# LED.net
KiCad netlist of a schematic drawn in Altium Designer
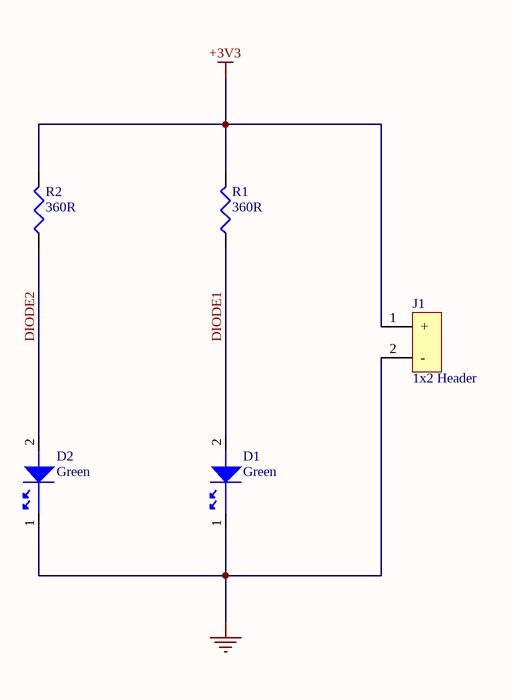
[diagram p0: LED.SchDoc]

(export (version "E")
  (design (tool "Eeschema 10.0.6"))
  (components
    (comp (ref "D1")
      (value "Green")
      (footprint "LED0603G")
      (description "APG1608CGKC/T Green LED; 570 nm 1608 (0603) Clear; Rectangle Lens SMD package")
      (fields
        (field (name "MANUFACTURER") "Kingbright")
        (field (name "MANUFACTURER PART NUMBER") "APG1608CGKC/T")
      )
      (libsource (lib "LED_Schlib1") (part "APG1608CGKC/T"))
    )
    (comp (ref "D2")
      (value "Green")
      (footprint "LED0603G")
      (description "APG1608CGKC/T Green LED; 570 nm 1608 (0603) Clear; Rectangle Lens SMD package")
      (fields
        (field (name "MANUFACTURER") "Kingbright")
        (field (name "MANUFACTURER PART NUMBER") "APG1608CGKC/T")
      )
      (libsource (lib "LED_Schlib1") (part "APG1608CGKC/T"))
    )
    (comp (ref "J1")
      (value "1x2 Header")
      (footprint "Header1x2")
      (description "KK 254 Wire-to-Board Header, Vertical, with Friction Lock, 2 Circuits, Gold (Au) Plating")
      (fields (field (name "MANUFACTURER") "Molex") (field (name "MANUFACTURER PART NUMBER") "22-29-2021"))
      (libsource (lib "LED_Schlib1") (part "22-29-2021"))
    )
    (comp (ref "R1")
      (value "360R")
      (footprint "R0805")
      (description "Res Thick Film 0805 36 Ohm 1% 1/8W ±100ppm/°C Molded SMD SMD Paper T/R")
      (fields
        (field (name "MANUFACTURER") "Vishay")
        (field (name "MANUFACTURER PART NUMBER") "CRCW080536R0FKEA")
      )
      (libsource (lib "LED_Schlib1") (part "CRCW080536R0FKEA"))
    )
    (comp (ref "R2")
      (value "360R")
      (footprint "R0805")
      (description "Res Thick Film 0805 36 Ohm 1% 1/8W ±100ppm/°C Molded SMD SMD Paper T/R")
      (fields
        (field (name "MANUFACTURER") "Vishay")
        (field (name "MANUFACTURER PART NUMBER") "CRCW080536R0FKEA")
      )
      (libsource (lib "LED_Schlib1") (part "CRCW080536R0FKEA"))
    )
  )
  (nets
    (net (code "1") (name "+3V3") (class "Default")
      (node (ref "J1") (pin "1") (pinfunction "+_1") (pintype "passive"))
      (node (ref "R1") (pin "2") (pinfunction "2_2") (pintype "passive"))
      (node (ref "R2") (pin "2") (pinfunction "2_2") (pintype "passive"))
    )
    (net (code "2") (name "/DIODE1") (class "Default")
      (node (ref "D1") (pin "2") (pinfunction "2_2") (pintype "passive"))
      (node (ref "R1") (pin "1") (pinfunction "1_1") (pintype "passive"))
    )
    (net (code "3") (name "/DIODE2") (class "Default")
      (node (ref "D2") (pin "2") (pinfunction "2_2") (pintype "passive"))
      (node (ref "R2") (pin "1") (pinfunction "1_1") (pintype "passive"))
    )
    (net (code "4") (name "GND") (class "Default")
      (node (ref "D1") (pin "1") (pinfunction "1_1") (pintype "passive"))
      (node (ref "D2") (pin "1") (pinfunction "1_1") (pintype "passive"))
      (node (ref "J1") (pin "2") (pinfunction "-_2") (pintype "passive"))
    )
  )
)
